# CPU_board_2A_7.net
KiCad netlist of a schematic drawn in EAGLE
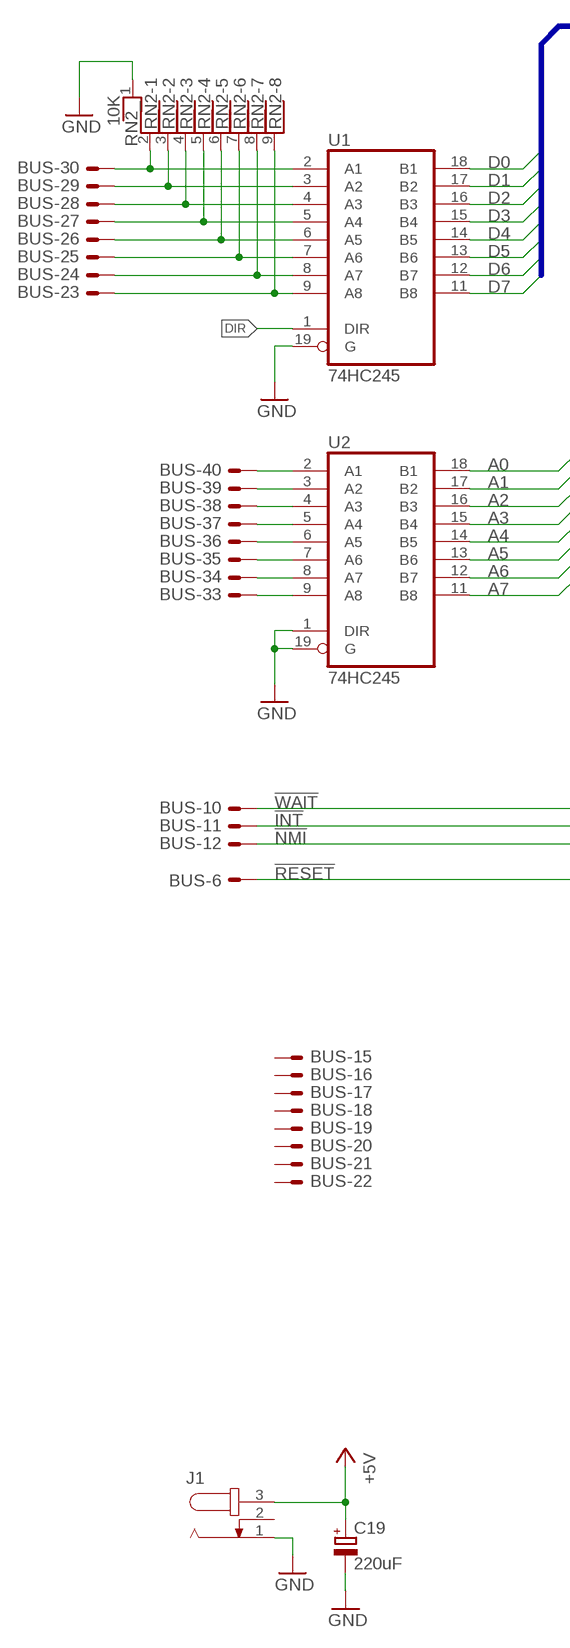
[diagram p0: schematic, sheet 1, part 1 of 2]
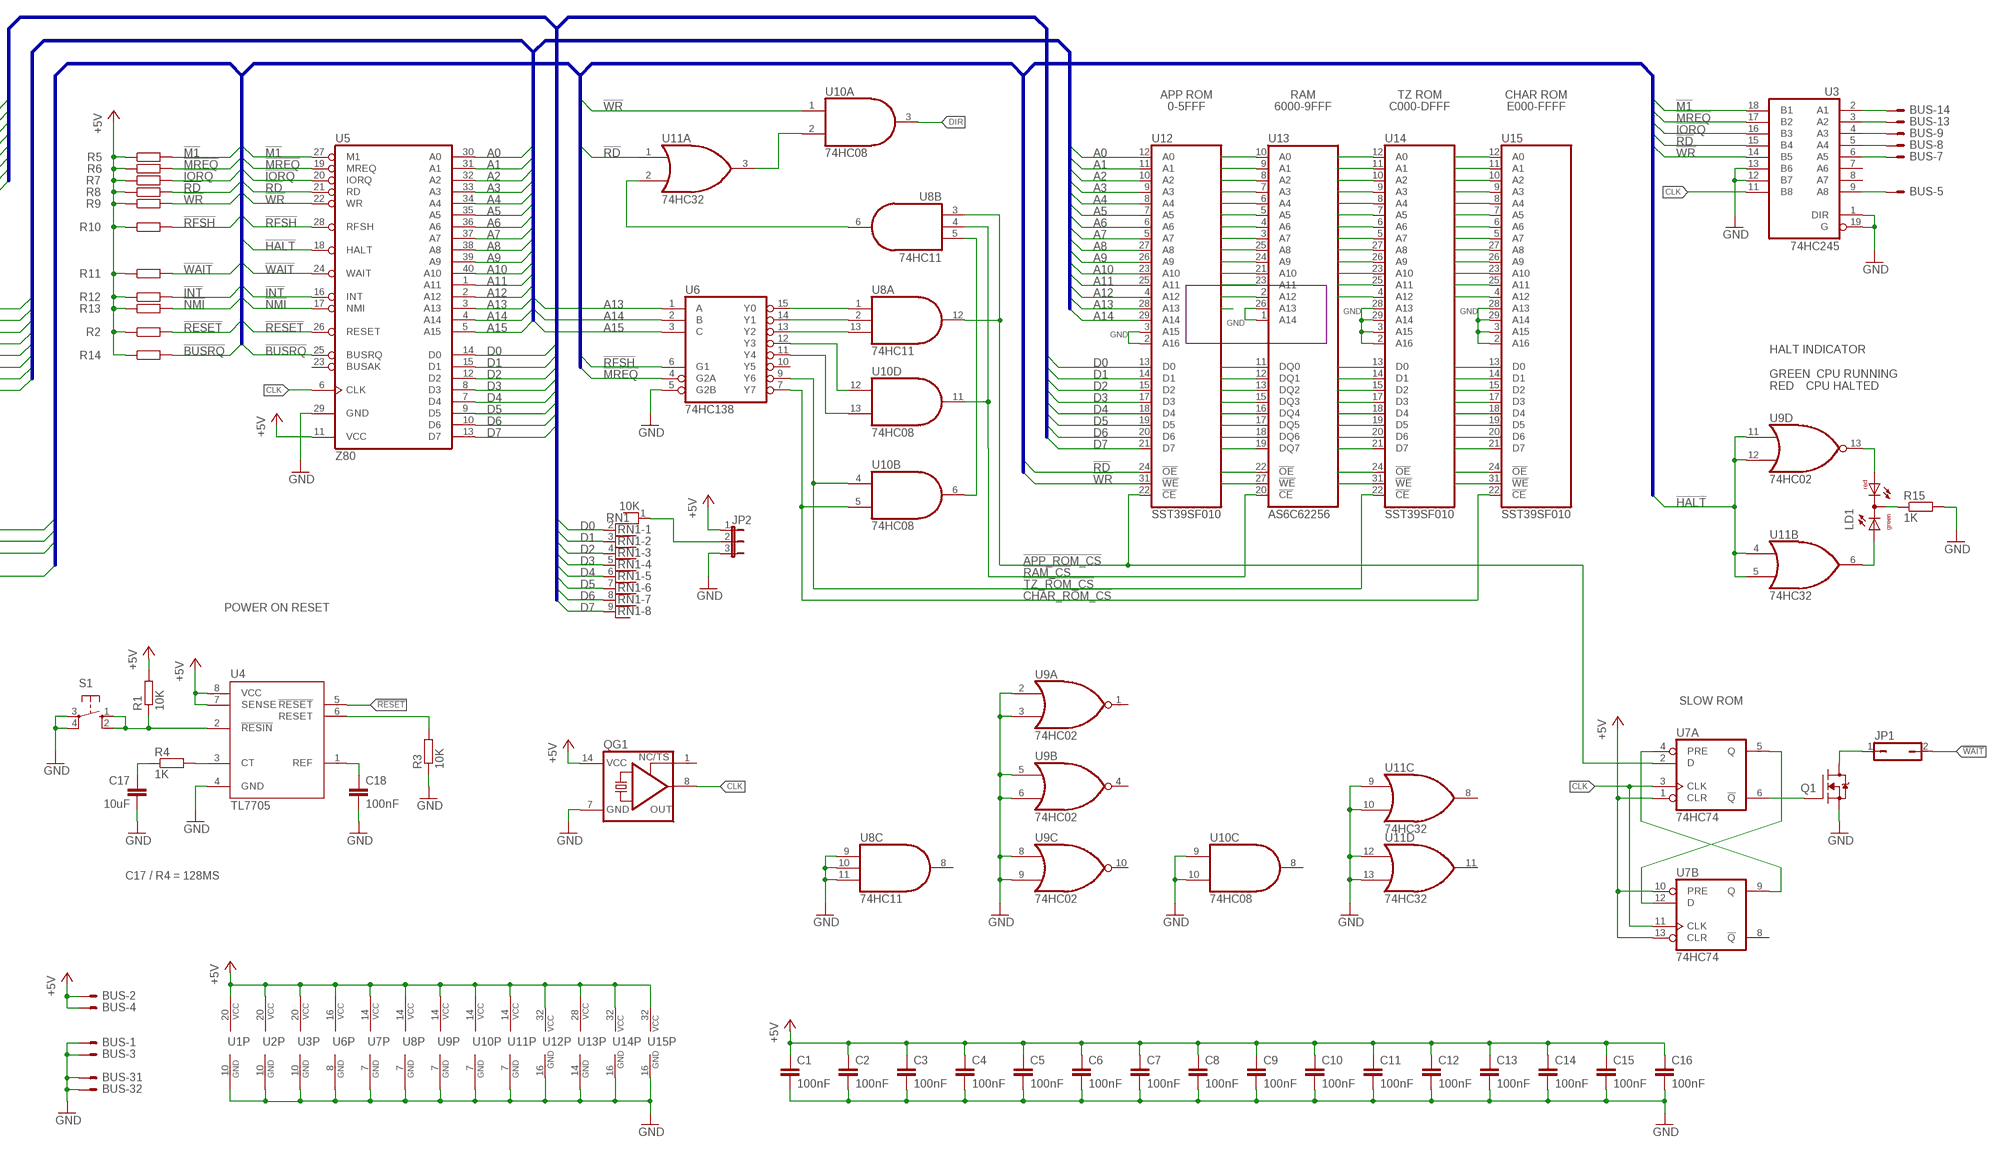
[diagram p1: schematic, sheet 1, part 2 of 2]

(export (version "E")
  (design (tool "Eeschema 10.0.6"))
  (components
    (comp (ref "BUS")
      (value "ML40E")
      (footprint "eagle-import:ML40")
      (libsource (lib "eagle-import") (part "ML40E"))
    )
    (comp (ref "C1")
      (value "100nF")
      (footprint "eagle-import:C050-025X075")
      (libsource (lib "eagle-import") (part "C-EU050-025X075"))
    )
    (comp (ref "C2")
      (value "100nF")
      (footprint "eagle-import:C050-025X075")
      (libsource (lib "eagle-import") (part "C-EU050-025X075"))
    )
    (comp (ref "C3")
      (value "100nF")
      (footprint "eagle-import:C050-025X075")
      (libsource (lib "eagle-import") (part "C-EU050-025X075"))
    )
    (comp (ref "C4")
      (value "100nF")
      (footprint "eagle-import:C050-025X075")
      (libsource (lib "eagle-import") (part "C-EU050-025X075"))
    )
    (comp (ref "C5")
      (value "100nF")
      (footprint "eagle-import:C050-025X075")
      (libsource (lib "eagle-import") (part "C-EU050-025X075"))
    )
    (comp (ref "C6")
      (value "100nF")
      (footprint "eagle-import:C050-025X075")
      (libsource (lib "eagle-import") (part "C-EU050-025X075"))
    )
    (comp (ref "C7")
      (value "100nF")
      (footprint "eagle-import:C050-025X075")
      (libsource (lib "eagle-import") (part "C-EU050-025X075"))
    )
    (comp (ref "C8")
      (value "100nF")
      (footprint "eagle-import:C050-025X075")
      (libsource (lib "eagle-import") (part "C-EU050-025X075"))
    )
    (comp (ref "C9")
      (value "100nF")
      (footprint "eagle-import:C050-025X075")
      (libsource (lib "eagle-import") (part "C-EU050-025X075"))
    )
    (comp (ref "C10")
      (value "100nF")
      (footprint "eagle-import:C050-025X075")
      (libsource (lib "eagle-import") (part "C-EU050-025X075"))
    )
    (comp (ref "C11")
      (value "100nF")
      (footprint "eagle-import:C050-025X075")
      (libsource (lib "eagle-import") (part "C-EU050-025X075"))
    )
    (comp (ref "C12")
      (value "100nF")
      (footprint "eagle-import:C050-025X075")
      (libsource (lib "eagle-import") (part "C-EU050-025X075"))
    )
    (comp (ref "C13")
      (value "100nF")
      (footprint "eagle-import:C050-025X075")
      (libsource (lib "eagle-import") (part "C-EU050-025X075"))
    )
    (comp (ref "C14")
      (value "100nF")
      (footprint "eagle-import:C050-025X075")
      (libsource (lib "eagle-import") (part "C-EU050-025X075"))
    )
    (comp (ref "C15")
      (value "100nF")
      (footprint "eagle-import:C050-025X075")
      (libsource (lib "eagle-import") (part "C-EU050-025X075"))
    )
    (comp (ref "C16")
      (value "100nF")
      (footprint "eagle-import:C050-025X075")
      (libsource (lib "eagle-import") (part "C-EU050-025X075"))
    )
    (comp (ref "C17")
      (value "10uF")
      (footprint "eagle-import:C050-025X075")
      (libsource (lib "eagle-import") (part "C-EU050-025X075"))
    )
    (comp (ref "C18")
      (value "100nF")
      (footprint "eagle-import:C050-025X075")
      (libsource (lib "eagle-import") (part "C-EU050-025X075"))
    )
    (comp (ref "C19")
      (value "220uF")
      (footprint "eagle-import:E3,5-8")
      (libsource (lib "eagle-import") (part "CPOL-EUE3.5-8"))
    )
    (comp (ref "J1")
      (value "JACK-PLUG0")
      (footprint "eagle-import:SPC4077")
      (libsource (lib "eagle-import") (part "JACK-PLUG0"))
    )
    (comp (ref "JP1")
      (value "JP1Q")
      (footprint "eagle-import:JP1")
      (libsource (lib "eagle-import") (part "JP1Q"))
    )
    (comp (ref "JP2")
      (value "JP2E")
      (footprint "eagle-import:JP2")
      (libsource (lib "eagle-import") (part "JP2E"))
    )
    (comp (ref "LD1")
      (value "DUOLED-RG-C")
      (footprint "eagle-import:DUOLED-C-5MM")
      (libsource (lib "eagle-import") (part "DUOLED-RG-C"))
    )
    (comp (ref "Q1")
      (value "2N7000")
      (footprint "eagle-import:TO-92-FORMED")
      (libsource (lib "eagle-import") (part "2N7000"))
    )
    (comp (ref "QG1")
      (value "XO-14")
      (footprint "eagle-import:DIL14S")
      (libsource (lib "eagle-import") (part "XO-14"))
    )
    (comp (ref "R1")
      (value "10K")
      (footprint "eagle-import:0207_10")
      (libsource (lib "eagle-import") (part "R-EU_0207/10"))
    )
    (comp (ref "R2")
      (value "10K")
      (footprint "eagle-import:0207_10")
      (libsource (lib "eagle-import") (part "R-EU_0207/10"))
    )
    (comp (ref "R3")
      (value "10K")
      (footprint "eagle-import:0207_10")
      (libsource (lib "eagle-import") (part "R-EU_0207/10"))
    )
    (comp (ref "R4")
      (value "1K")
      (footprint "eagle-import:0207_10")
      (libsource (lib "eagle-import") (part "R-EU_0207/10"))
    )
    (comp (ref "R5")
      (value "R-EU_0207/10")
      (footprint "eagle-import:0207_10")
      (libsource (lib "eagle-import") (part "R-EU_0207/10"))
    )
    (comp (ref "R6")
      (value "R-EU_0207/10")
      (footprint "eagle-import:0207_10")
      (libsource (lib "eagle-import") (part "R-EU_0207/10"))
    )
    (comp (ref "R7")
      (value "R-EU_0207/10")
      (footprint "eagle-import:0207_10")
      (libsource (lib "eagle-import") (part "R-EU_0207/10"))
    )
    (comp (ref "R8")
      (value "R-EU_0207/10")
      (footprint "eagle-import:0207_10")
      (libsource (lib "eagle-import") (part "R-EU_0207/10"))
    )
    (comp (ref "R9")
      (value "R-EU_0207/10")
      (footprint "eagle-import:0207_10")
      (libsource (lib "eagle-import") (part "R-EU_0207/10"))
    )
    (comp (ref "R10")
      (value "R-EU_0207/10")
      (footprint "eagle-import:0207_10")
      (libsource (lib "eagle-import") (part "R-EU_0207/10"))
    )
    (comp (ref "R11")
      (value "R-EU_0207/10")
      (footprint "eagle-import:0207_10")
      (libsource (lib "eagle-import") (part "R-EU_0207/10"))
    )
    (comp (ref "R12")
      (value "R-EU_0207/10")
      (footprint "eagle-import:0207_10")
      (libsource (lib "eagle-import") (part "R-EU_0207/10"))
    )
    (comp (ref "R13")
      (value "R-EU_0207/10")
      (footprint "eagle-import:0207_10")
      (libsource (lib "eagle-import") (part "R-EU_0207/10"))
    )
    (comp (ref "R14")
      (value "R-EU_0207/10")
      (footprint "eagle-import:0207_10")
      (libsource (lib "eagle-import") (part "R-EU_0207/10"))
    )
    (comp (ref "R15")
      (value "1K")
      (footprint "eagle-import:0207_10")
      (libsource (lib "eagle-import") (part "R-EU_0207/10"))
    )
    (comp (ref "RN1")
      (value "10K")
      (footprint "eagle-import:RN-9")
      (libsource (lib "eagle-import") (part "RNX8"))
    )
    (comp (ref "RN2")
      (value "10K")
      (footprint "eagle-import:RN-9")
      (libsource (lib "eagle-import") (part "RNX8"))
    )
    (comp (ref "S1")
      (value "10-XX")
      (footprint "eagle-import:B3F-10XX")
      (fields (field (name "MPN") "B3F-1000"))
      (libsource (lib "eagle-import") (part "10-XX"))
    )
    (comp (ref "U1")
      (value "74HC245")
      (footprint "eagle-import:DIL20")
      (libsource (lib "eagle-import") (part "74245NLS"))
    )
    (comp (ref "U2")
      (value "74HC245")
      (footprint "eagle-import:DIL20")
      (libsource (lib "eagle-import") (part "74245NLS"))
    )
    (comp (ref "U3")
      (value "74HC245")
      (footprint "eagle-import:DIL20")
      (libsource (lib "eagle-import") (part "74245NLS"))
    )
    (comp (ref "U4")
      (value "TL7705")
      (footprint "eagle-import:DIL08")
      (libsource (lib "eagle-import") (part "TL77XXA"))
    )
    (comp (ref "U5")
      (value "Z80")
      (footprint "eagle-import:DIL40")
      (libsource (lib "eagle-import") (part "Z80CPU"))
    )
    (comp (ref "U6")
      (value "74HC138")
      (footprint "eagle-import:DIL16")
      (libsource (lib "eagle-import") (part "74138NLS"))
    )
    (comp (ref "U7")
      (value "74HC74")
      (footprint "eagle-import:DIL14")
      (libsource (lib "eagle-import") (part "7474NLS"))
    )
    (comp (ref "U8")
      (value "74HC11")
      (footprint "eagle-import:DIL14")
      (libsource (lib "eagle-import") (part "7411NLS"))
    )
    (comp (ref "U9")
      (value "74HC02")
      (footprint "eagle-import:DIL14")
      (libsource (lib "eagle-import") (part "7402NLS"))
    )
    (comp (ref "U10")
      (value "74HC08")
      (footprint "eagle-import:DIL14")
      (libsource (lib "eagle-import") (part "7408NLS"))
    )
    (comp (ref "U11")
      (value "74HC32")
      (footprint "eagle-import:DIL14")
      (libsource (lib "eagle-import") (part "7432NLS"))
    )
    (comp (ref "U12")
      (value "SST39SF010")
      (footprint "eagle-import:DIL32")
      (libsource (lib "eagle-import") (part "SST39SF010P"))
    )
    (comp (ref "U13")
      (value "AS6C62256")
      (footprint "eagle-import:DIL28-6")
      (libsource (lib "eagle-import") (part "AS6C62256-55PCN"))
    )
    (comp (ref "U14")
      (value "SST39SF010")
      (footprint "eagle-import:PLCC-SR32")
      (libsource (lib "eagle-import") (part "SST39SF010NS"))
    )
    (comp (ref "U15")
      (value "SST39SF010")
      (footprint "eagle-import:PLCC-SR32")
      (libsource (lib "eagle-import") (part "SST39SF010NS"))
    )
  )
  (nets
    (net (code "18") (name "+5V") (class "Default")
      (node (ref "BUS") (pin "2") (pinfunction "S_2") (pintype "passive"))
      (node (ref "BUS") (pin "4") (pinfunction "S_4") (pintype "passive"))
      (node (ref "C1") (pin "1") (pinfunction "1_1") (pintype "passive"))
      (node (ref "C10") (pin "1") (pinfunction "1_1") (pintype "passive"))
      (node (ref "C11") (pin "1") (pinfunction "1_1") (pintype "passive"))
      (node (ref "C12") (pin "1") (pinfunction "1_1") (pintype "passive"))
      (node (ref "C13") (pin "1") (pinfunction "1_1") (pintype "passive"))
      (node (ref "C14") (pin "1") (pinfunction "1_1") (pintype "passive"))
      (node (ref "C15") (pin "1") (pinfunction "1_1") (pintype "passive"))
      (node (ref "C16") (pin "1") (pinfunction "1_1") (pintype "passive"))
      (node (ref "C19") (pin "+") (pinfunction "+_+") (pintype "passive"))
      (node (ref "C2") (pin "1") (pinfunction "1_1") (pintype "passive"))
      (node (ref "C3") (pin "1") (pinfunction "1_1") (pintype "passive"))
      (node (ref "C4") (pin "1") (pinfunction "1_1") (pintype "passive"))
      (node (ref "C5") (pin "1") (pinfunction "1_1") (pintype "passive"))
      (node (ref "C6") (pin "1") (pinfunction "1_1") (pintype "passive"))
      (node (ref "C7") (pin "1") (pinfunction "1_1") (pintype "passive"))
      (node (ref "C8") (pin "1") (pinfunction "1_1") (pintype "passive"))
      (node (ref "C9") (pin "1") (pinfunction "1_1") (pintype "passive"))
      (node (ref "J1") (pin "3") (pinfunction "3_3") (pintype "passive"))
      (node (ref "JP2") (pin "1") (pinfunction "1_1") (pintype "passive"))
      (node (ref "QG1") (pin "14") (pinfunction "VCC_14") (pintype "power_in"))
      (node (ref "R1") (pin "2") (pinfunction "2_2") (pintype "passive"))
      (node (ref "R10") (pin "1") (pinfunction "1_1") (pintype "passive"))
      (node (ref "R11") (pin "1") (pinfunction "1_1") (pintype "passive"))
      (node (ref "R12") (pin "1") (pinfunction "1_1") (pintype "passive"))
      (node (ref "R13") (pin "1") (pinfunction "1_1") (pintype "passive"))
      (node (ref "R14") (pin "1") (pinfunction "1_1") (pintype "passive"))
      (node (ref "R2") (pin "1") (pinfunction "1_1") (pintype "passive"))
      (node (ref "R5") (pin "1") (pinfunction "1_1") (pintype "passive"))
      (node (ref "R6") (pin "1") (pinfunction "1_1") (pintype "passive"))
      (node (ref "R7") (pin "1") (pinfunction "1_1") (pintype "passive"))
      (node (ref "R8") (pin "1") (pinfunction "1_1") (pintype "passive"))
      (node (ref "R9") (pin "1") (pinfunction "1_1") (pintype "passive"))
      (node (ref "U1") (pin "20") (pinfunction "VCC_20") (pintype "power_in"))
      (node (ref "U10") (pin "14") (pinfunction "VCC_14") (pintype "power_in"))
      (node (ref "U11") (pin "14") (pinfunction "VCC_14") (pintype "power_in"))
      (node (ref "U12") (pin "32") (pinfunction "VCC_32") (pintype "power_in"))
      (node (ref "U13") (pin "28") (pinfunction "VCC_28") (pintype "power_in"))
      (node (ref "U14") (pin "32") (pinfunction "VCC_32") (pintype "power_in"))
      (node (ref "U15") (pin "32") (pinfunction "VCC_32") (pintype "power_in"))
      (node (ref "U2") (pin "20") (pinfunction "VCC_20") (pintype "power_in"))
      (node (ref "U3") (pin "20") (pinfunction "VCC_20") (pintype "power_in"))
      (node (ref "U4") (pin "7") (pinfunction "SENSE_7") (pintype "input"))
      (node (ref "U4") (pin "8") (pinfunction "VCC_8") (pintype "power_in"))
      (node (ref "U5") (pin "11") (pinfunction "VCC_11") (pintype "power_in"))
      (node (ref "U6") (pin "16") (pinfunction "VCC_16") (pintype "power_in"))
      (node (ref "U7") (pin "1") (pinfunction "CLR_1") (pintype "input"))
      (node (ref "U7") (pin "10") (pinfunction "PRE_10") (pintype "input"))
      (node (ref "U7") (pin "13") (pinfunction "CLR_13") (pintype "input"))
      (node (ref "U7") (pin "14") (pinfunction "VCC_14") (pintype "power_in"))
      (node (ref "U8") (pin "14") (pinfunction "VCC_14") (pintype "power_in"))
      (node (ref "U9") (pin "14") (pinfunction "VCC_14") (pintype "power_in"))
    )
    (net (code "21") (name "A0") (class "Default")
      (node (ref "U12") (pin "12") (pinfunction "A0_12") (pintype "input"))
      (node (ref "U13") (pin "10") (pinfunction "A0_10") (pintype "input"))
      (node (ref "U14") (pin "12") (pinfunction "A0_12") (pintype "input"))
      (node (ref "U15") (pin "12") (pinfunction "A0_12") (pintype "input"))
      (node (ref "U2") (pin "18") (pinfunction "B1_18") (pintype "bidirectional"))
      (node (ref "U5") (pin "30") (pinfunction "A0_30") (pintype "output"))
    )
    (net (code "22") (name "A1") (class "Default")
      (node (ref "U12") (pin "11") (pinfunction "A1_11") (pintype "input"))
      (node (ref "U13") (pin "9") (pinfunction "A1_9") (pintype "input"))
      (node (ref "U14") (pin "11") (pinfunction "A1_11") (pintype "input"))
      (node (ref "U15") (pin "11") (pinfunction "A1_11") (pintype "input"))
      (node (ref "U2") (pin "17") (pinfunction "B2_17") (pintype "bidirectional"))
      (node (ref "U5") (pin "31") (pinfunction "A1_31") (pintype "output"))
    )
    (net (code "23") (name "A2") (class "Default")
      (node (ref "U12") (pin "10") (pinfunction "A2_10") (pintype "input"))
      (node (ref "U13") (pin "8") (pinfunction "A2_8") (pintype "input"))
      (node (ref "U14") (pin "10") (pinfunction "A2_10") (pintype "input"))
      (node (ref "U15") (pin "10") (pinfunction "A2_10") (pintype "input"))
      (node (ref "U2") (pin "16") (pinfunction "B3_16") (pintype "bidirectional"))
      (node (ref "U5") (pin "32") (pinfunction "A2_32") (pintype "output"))
    )
    (net (code "24") (name "A3") (class "Default")
      (node (ref "U12") (pin "9") (pinfunction "A3_9") (pintype "input"))
      (node (ref "U13") (pin "7") (pinfunction "A3_7") (pintype "input"))
      (node (ref "U14") (pin "9") (pinfunction "A3_9") (pintype "input"))
      (node (ref "U15") (pin "9") (pinfunction "A3_9") (pintype "input"))
      (node (ref "U2") (pin "15") (pinfunction "B4_15") (pintype "bidirectional"))
      (node (ref "U5") (pin "33") (pinfunction "A3_33") (pintype "output"))
    )
    (net (code "25") (name "A4") (class "Default")
      (node (ref "U12") (pin "8") (pinfunction "A4_8") (pintype "input"))
      (node (ref "U13") (pin "6") (pinfunction "A4_6") (pintype "input"))
      (node (ref "U14") (pin "8") (pinfunction "A4_8") (pintype "input"))
      (node (ref "U15") (pin "8") (pinfunction "A4_8") (pintype "input"))
      (node (ref "U2") (pin "14") (pinfunction "B5_14") (pintype "bidirectional"))
      (node (ref "U5") (pin "34") (pinfunction "A4_34") (pintype "output"))
    )
    (net (code "26") (name "A5") (class "Default")
      (node (ref "U12") (pin "7") (pinfunction "A5_7") (pintype "input"))
      (node (ref "U13") (pin "5") (pinfunction "A5_5") (pintype "input"))
      (node (ref "U14") (pin "7") (pinfunction "A5_7") (pintype "input"))
      (node (ref "U15") (pin "7") (pinfunction "A5_7") (pintype "input"))
      (node (ref "U2") (pin "13") (pinfunction "B6_13") (pintype "bidirectional"))
      (node (ref "U5") (pin "35") (pinfunction "A5_35") (pintype "output"))
    )
    (net (code "27") (name "A6") (class "Default")
      (node (ref "U12") (pin "6") (pinfunction "A6_6") (pintype "input"))
      (node (ref "U13") (pin "4") (pinfunction "A6_4") (pintype "input"))
      (node (ref "U14") (pin "6") (pinfunction "A6_6") (pintype "input"))
      (node (ref "U15") (pin "6") (pinfunction "A6_6") (pintype "input"))
      (node (ref "U2") (pin "12") (pinfunction "B7_12") (pintype "bidirectional"))
      (node (ref "U5") (pin "36") (pinfunction "A6_36") (pintype "output"))
    )
    (net (code "28") (name "A7") (class "Default")
      (node (ref "U12") (pin "5") (pinfunction "A7_5") (pintype "input"))
      (node (ref "U13") (pin "3") (pinfunction "A7_3") (pintype "input"))
      (node (ref "U14") (pin "5") (pinfunction "A7_5") (pintype "input"))
      (node (ref "U15") (pin "5") (pinfunction "A7_5") (pintype "input"))
      (node (ref "U2") (pin "11") (pinfunction "B8_11") (pintype "bidirectional"))
      (node (ref "U5") (pin "37") (pinfunction "A7_37") (pintype "output"))
    )
    (net (code "29") (name "A8") (class "Default")
      (node (ref "U12") (pin "27") (pinfunction "A8_27") (pintype "input"))
      (node (ref "U13") (pin "25") (pinfunction "A8_25") (pintype "input"))
      (node (ref "U14") (pin "27") (pinfunction "A8_27") (pintype "input"))
      (node (ref "U15") (pin "27") (pinfunction "A8_27") (pintype "input"))
      (node (ref "U5") (pin "38") (pinfunction "A8_38") (pintype "output"))
    )
    (net (code "30") (name "A9") (class "Default")
      (node (ref "U12") (pin "26") (pinfunction "A9_26") (pintype "input"))
      (node (ref "U13") (pin "24") (pinfunction "A9_24") (pintype "input"))
      (node (ref "U14") (pin "26") (pinfunction "A9_26") (pintype "input"))
      (node (ref "U15") (pin "26") (pinfunction "A9_26") (pintype "input"))
      (node (ref "U5") (pin "39") (pinfunction "A9_39") (pintype "output"))
    )
    (net (code "31") (name "A10") (class "Default")
      (node (ref "U12") (pin "23") (pinfunction "A10_23") (pintype "input"))
      (node (ref "U13") (pin "21") (pinfunction "A10_21") (pintype "input"))
      (node (ref "U14") (pin "23") (pinfunction "A10_23") (pintype "input"))
      (node (ref "U15") (pin "23") (pinfunction "A10_23") (pintype "input"))
      (node (ref "U5") (pin "40") (pinfunction "A10_40") (pintype "output"))
    )
    (net (code "32") (name "A11") (class "Default")
      (node (ref "U12") (pin "25") (pinfunction "A11_25") (pintype "input"))
      (node (ref "U13") (pin "23") (pinfunction "A11_23") (pintype "input"))
      (node (ref "U14") (pin "25") (pinfunction "A11_25") (pintype "input"))
      (node (ref "U15") (pin "25") (pinfunction "A11_25") (pintype "input"))
      (node (ref "U5") (pin "1") (pinfunction "A11_1") (pintype "output"))
    )
    (net (code "33") (name "A12") (class "Default")
      (node (ref "U12") (pin "4") (pinfunction "A12_4") (pintype "input"))
      (node (ref "U13") (pin "2") (pinfunction "A12_2") (pintype "input"))
      (node (ref "U14") (pin "4") (pinfunction "A12_4") (pintype "input"))
      (node (ref "U15") (pin "4") (pinfunction "A12_4") (pintype "input"))
      (node (ref "U5") (pin "2") (pinfunction "A12_2") (pintype "output"))
    )
    (net (code "34") (name "A13") (class "Default")
      (node (ref "U12") (pin "28") (pinfunction "A13_28") (pintype "input"))
      (node (ref "U5") (pin "3") (pinfunction "A13_3") (pintype "output"))
      (node (ref "U6") (pin "1") (pinfunction "A_1") (pintype "input"))
    )
    (net (code "35") (name "A14") (class "Default")
      (node (ref "U12") (pin "29") (pinfunction "A14_29") (pintype "input"))
      (node (ref "U5") (pin "4") (pinfunction "A14_4") (pintype "output"))
      (node (ref "U6") (pin "2") (pinfunction "B_2") (pintype "input"))
    )
    (net (code "36") (name "A15") (class "Default")
      (node (ref "U5") (pin "5") (pinfunction "A15_5") (pintype "output"))
      (node (ref "U6") (pin "3") (pinfunction "C_3") (pintype "input"))
    )
    (net (code "37") (name "CLK") (class "Default")
      (node (ref "QG1") (pin "8") (pinfunction "OUT_8") (pintype "output"))
      (node (ref "U3") (pin "11") (pinfunction "B8_11") (pintype "bidirectional"))
      (node (ref "U5") (pin "6") (pinfunction "CLK_6") (pintype "input"))
      (node (ref "U7") (pin "11") (pinfunction "CLK_11") (pintype "input"))
      (node (ref "U7") (pin "3") (pinfunction "CLK_3") (pintype "input"))
    )
    (net (code "38") (name "D0") (class "Default")
      (node (ref "RN1") (pin "2") (pinfunction "1_2") (pintype "passive"))
      (node (ref "U1") (pin "18") (pinfunction "B1_18") (pintype "bidirectional"))
      (node (ref "U12") (pin "13") (pinfunction "D0_13") (pintype "bidirectional"))
      (node (ref "U13") (pin "11") (pinfunction "DQ0_11") (pintype "bidirectional"))
      (node (ref "U14") (pin "13") (pinfunction "D0_13") (pintype "bidirectional"))
      (node (ref "U15") (pin "13") (pinfunction "D0_13") (pintype "bidirectional"))
      (node (ref "U5") (pin "14") (pinfunction "D0_14") (pintype "bidirectional"))
    )
    (net (code "39") (name "D1") (class "Default")
      (node (ref "RN1") (pin "3") (pinfunction "1_3") (pintype "passive"))
      (node (ref "U1") (pin "17") (pinfunction "B2_17") (pintype "bidirectional"))
      (node (ref "U12") (pin "14") (pinfunction "D1_14") (pintype "bidirectional"))
      (node (ref "U13") (pin "12") (pinfunction "DQ1_12") (pintype "bidirectional"))
      (node (ref "U14") (pin "14") (pinfunction "D1_14") (pintype "bidirectional"))
      (node (ref "U15") (pin "14") (pinfunction "D1_14") (pintype "bidirectional"))
      (node (ref "U5") (pin "15") (pinfunction "D1_15") (pintype "bidirectional"))
    )
    (net (code "40") (name "D2") (class "Default")
      (node (ref "RN1") (pin "4") (pinfunction "1_4") (pintype "passive"))
      (node (ref "U1") (pin "16") (pinfunction "B3_16") (pintype "bidirectional"))
      (node (ref "U12") (pin "15") (pinfunction "D2_15") (pintype "bidirectional"))
      (node (ref "U13") (pin "13") (pinfunction "DQ2_13") (pintype "bidirectional"))
      (node (ref "U14") (pin "15") (pinfunction "D2_15") (pintype "bidirectional"))
      (node (ref "U15") (pin "15") (pinfunction "D2_15") (pintype "bidirectional"))
      (node (ref "U5") (pin "12") (pinfunction "D2_12") (pintype "bidirectional"))
    )
    (net (code "41") (name "D3") (class "Default")
      (node (ref "RN1") (pin "5") (pinfunction "1_5") (pintype "passive"))
      (node (ref "U1") (pin "15") (pinfunction "B4_15") (pintype "bidirectional"))
      (node (ref "U12") (pin "17") (pinfunction "D3_17") (pintype "bidirectional"))
      (node (ref "U13") (pin "15") (pinfunction "DQ3_15") (pintype "bidirectional"))
      (node (ref "U14") (pin "17") (pinfunction "D3_17") (pintype "bidirectional"))
      (node (ref "U15") (pin "17") (pinfunction "D3_17") (pintype "bidirectional"))
      (node (ref "U5") (pin "8") (pinfunction "D3_8") (pintype "bidirectional"))
    )
    (net (code "42") (name "D4") (class "Default")
      (node (ref "RN1") (pin "6") (pinfunction "1_6") (pintype "passive"))
      (node (ref "U1") (pin "14") (pinfunction "B5_14") (pintype "bidirectional"))
      (node (ref "U12") (pin "18") (pinfunction "D4_18") (pintype "bidirectional"))
      (node (ref "U13") (pin "16") (pinfunction "DQ4_16") (pintype "bidirectional"))
      (node (ref "U14") (pin "18") (pinfunction "D4_18") (pintype "bidirectional"))
      (node (ref "U15") (pin "18") (pinfunction "D4_18") (pintype "bidirectional"))
      (node (ref "U5") (pin "7") (pinfunction "D4_7") (pintype "bidirectional"))
    )
    (net (code "43") (name "D5") (class "Default")
      (node (ref "RN1") (pin "7") (pinfunction "1_7") (pintype "passive"))
      (node (ref "U1") (pin "13") (pinfunction "B6_13") (pintype "bidirectional"))
      (node (ref "U12") (pin "19") (pinfunction "D5_19") (pintype "bidirectional"))
      (node (ref "U13") (pin "17") (pinfunction "DQ5_17") (pintype "bidirectional"))
      (node (ref "U14") (pin "19") (pinfunction "D5_19") (pintype "bidirectional"))
      (node (ref "U15") (pin "19") (pinfunction "D5_19") (pintype "bidirectional"))
      (node (ref "U5") (pin "9") (pinfunction "D5_9") (pintype "bidirectional"))
    )
    (net (code "44") (name "D6") (class "Default")
      (node (ref "RN1") (pin "8") (pinfunction "1_8") (pintype "passive"))
      (node (ref "U1") (pin "12") (pinfunction "B7_12") (pintype "bidirectional"))
      (node (ref "U12") (pin "20") (pinfunction "D6_20") (pintype "bidirectional"))
      (node (ref "U13") (pin "18") (pinfunction "DQ6_18") (pintype "bidirectional"))
      (node (ref "U14") (pin "20") (pinfunction "D6_20") (pintype "bidirectional"))
      (node (ref "U15") (pin "20") (pinfunction "D6_20") (pintype "bidirectional"))
      (node (ref "U5") (pin "10") (pinfunction "D6_10") (pintype "bidirectional"))
    )
    (net (code "45") (name "D7") (class "Default")
      (node (ref "RN1") (pin "9") (pinfunction "1_9") (pintype "passive"))
      (node (ref "U1") (pin "11") (pinfunction "B8_11") (pintype "bidirectional"))
      (node (ref "U12") (pin "21") (pinfunction "D7_21") (pintype "bidirectional"))
      (node (ref "U13") (pin "19") (pinfunction "DQ7_19") (pintype "bidirectional"))
      (node (ref "U14") (pin "21") (pinfunction "D7_21") (pintype "bidirectional"))
      (node (ref "U15") (pin "21") (pinfunction "D7_21") (pintype "bidirectional"))
      (node (ref "U5") (pin "13") (pinfunction "D7_13") (pintype "bidirectional"))
    )
    (net (code "46") (name "DIR") (class "Default")
      (node (ref "U1") (pin "1") (pinfunction "DIR_1") (pintype "input"))
      (node (ref "U10") (pin "3") (pinfunction "O_3") (pintype "output"))
    )
    (net (code "47") (name "GND") (class "Default")
      (node (ref "BUS") (pin "1") (pinfunction "S_1") (pintype "passive"))
      (node (ref "BUS") (pin "3") (pinfunction "S_3") (pintype "passive"))
      (node (ref "BUS") (pin "31") (pinfunction "S_31") (pintype "passive"))
      (node (ref "BUS") (pin "32") (pinfunction "S_32") (pintype "passive"))
      (node (ref "C1") (pin "2") (pinfunction "2_2") (pintype "passive"))
      (node (ref "C10") (pin "2") (pinfunction "2_2") (pintype "passive"))
      (node (ref "C11") (pin "2") (pinfunction "2_2") (pintype "passive"))
      (node (ref "C12") (pin "2") (pinfunction "2_2") (pintype "passive"))
      (node (ref "C13") (pin "2") (pinfunction "2_2") (pintype "passive"))
      (node (ref "C14") (pin "2") (pinfunction "2_2") (pintype "passive"))
      (node (ref "C15") (pin "2") (pinfunction "2_2") (pintype "passive"))
      (node (ref "C16") (pin "2") (pinfunction "2_2") (pintype "passive"))
      (node (ref "C17") (pin "2") (pinfunction "2_2") (pintype "passive"))
      (node (ref "C18") (pin "2") (pinfunction "2_2") (pintype "passive"))
      (node (ref "C19") (pin "-") (pinfunction "-_-") (pintype "passive"))
      (node (ref "C2") (pin "2") (pinfunction "2_2") (pintype "passive"))
      (node (ref "C3") (pin "2") (pinfunction "2_2") (pintype "passive"))
      (node (ref "C4") (pin "2") (pinfunction "2_2") (pintype "passive"))
      (node (ref "C5") (pin "2") (pinfunction "2_2") (pintype "passive"))
      (node (ref "C6") (pin "2") (pinfunction "2_2") (pintype "passive"))
      (node (ref "C7") (pin "2") (pinfunction "2_2") (pintype "passive"))
      (node (ref "C8") (pin "2") (pinfunction "2_2") (pintype "passive"))
      (node (ref "C9") (pin "2") (pinfunction "2_2") (pintype "passive"))
      (node (ref "J1") (pin "1") (pinfunction "1_1") (pintype "passive"))
      (node (ref "JP2") (pin "3") (pinfunction "3_3") (pintype "passive"))
      (node (ref "Q1") (pin "1") (pinfunction "S_1") (pintype "passive"))
      (node (ref "QG1") (pin "7") (pinfunction "GND_7") (pintype "power_in"))
      (node (ref "R15") (pin "2") (pinfunction "2_2") (pintype "passive"))
      (node (ref "R3") (pin "1") (pinfunction "1_1") (pintype "passive"))
      (node (ref "RN2") (pin "1") (pinfunction "1_1") (pintype "passive"))
      (node (ref "S1") (pin "3") (pinfunction "P_3") (pintype "passive"))
      (node (ref "S1") (pin "4") (pinfunction "P1_4") (pintype "passive"))
      (node (ref "U1") (pin "10") (pinfunction "GND_10") (pintype "power_in"))
      (node (ref "U1") (pin "19") (pinfunction "G_19") (pintype "input"))
      (node (ref "U10") (pin "10") (pinfunction "I1_10") (pintype "input"))
      (node (ref "U10") (pin "7") (pinfunction "GND_7") (pintype "power_in"))
      (node (ref "U10") (pin "9") (pinfunction "I0_9") (pintype "input"))
      (node (ref "U11") (pin "10") (pinfunction "I1_10") (pintype "input"))
      (node (ref "U11") (pin "12") (pinfunction "I0_12") (pintype "input"))
      (node (ref "U11") (pin "13") (pinfunction "I1_13") (pintype "input"))
      (node (ref "U11") (pin "7") (pinfunction "GND_7") (pintype "power_in"))
      (node (ref "U11") (pin "9") (pinfunction "I0_9") (pintype "input"))
      (node (ref "U12") (pin "16") (pinfunction "GND_16") (pintype "power_in"))
      (node (ref "U12") (pin "2") (pinfunction "A16_2") (pintype "input"))
      (node (ref "U12") (pin "3") (pinfunction "A15_3") (pintype "input"))
      (node (ref "U13") (pin "1") (pinfunction "A14_1") (pintype "input"))
      (node (ref "U13") (pin "14") (pinfunction "GND_14") (pintype "power_in"))
      (node (ref "U13") (pin "26") (pinfunction "A13_26") (pintype "input"))
      (node (ref "U14") (pin "16") (pinfunction "GND_16") (pintype "power_in"))
      (node (ref "U14") (pin "2") (pinfunction "A16_2") (pintype "input"))
      (node (ref "U14") (pin "28") (pinfunction "A13_28") (pintype "input"))
      (node (ref "U14") (pin "29") (pinfunction "A14_29") (pintype "input"))
      (node (ref "U14") (pin "3") (pinfunction "A15_3") (pintype "input"))
      (node (ref "U15") (pin "16") (pinfunction "GND_16") (pintype "power_in"))
      (node (ref "U15") (pin "2") (pinfunction "A16_2") (pintype "input"))
      (node (ref "U15") (pin "28") (pinfunction "A13_28") (pintype "input"))
      (node (ref "U15") (pin "29") (pinfunction "A14_29") (pintype "input"))
      (node (ref "U15") (pin "3") (pinfunction "A15_3") (pintype "input"))
      (node (ref "U2") (pin "1") (pinfunction "DIR_1") (pintype "input"))
      (node (ref "U2") (pin "10") (pinfunction "GND_10") (pintype "power_in"))
      (node (ref "U2") (pin "19") (pinfunction "G_19") (pintype "input"))
      (node (ref "U3") (pin "1") (pinfunction "DIR_1") (pintype "input"))
      (node (ref "U3") (pin "10") (pinfunction "GND_10") (pintype "power_in"))
      (node (ref "U3") (pin "12") (pinfunction "B7_12") (pintype "bidirectional"))
      (node (ref "U3") (pin "13") (pinfunction "B6_13") (pintype "bidirectional"))
      (node (ref "U3") (pin "19") (pinfunction "G_19") (pintype "input"))
      (node (ref "U4") (pin "4") (pinfunction "GND_4") (pintype "power_in"))
      (node (ref "U5") (pin "29") (pinfunction "GND_29") (pintype "power_in"))
      (node (ref "U6") (pin "5") (pinfunction "G2B_5") (pintype "input"))
      (node (ref "U6") (pin "8") (pinfunction "GND_8") (pintype "power_in"))
      (node (ref "U7") (pin "7") (pinfunction "GND_7") (pintype "power_in"))
      (node (ref "U8") (pin "10") (pinfunction "I1_10") (pintype "input"))
      (node (ref "U8") (pin "11") (pinfunction "I2_11") (pintype "input"))
      (node (ref "U8") (pin "7") (pinfunction "GND_7") (pintype "power_in"))
      (node (ref "U8") (pin "9") (pinfunction "I0_9") (pintype "input"))
      (node (ref "U9") (pin "2") (pinfunction "I0_2") (pintype "input"))
      (node (ref "U9") (pin "3") (pinfunction "I1_3") (pintype "input"))
      (node (ref "U9") (pin "5") (pinfunction "I0_5") (pintype "input"))
      (node (ref "U9") (pin "6") (pinfunction "I1_6") (pintype "input"))
      (node (ref "U9") (pin "7") (pinfunction "GND_7") (pintype "power_in"))
      (node (ref "U9") (pin "8") (pinfunction "I0_8") (pintype "input"))
      (node (ref "U9") (pin "9") (pinfunction "I1_9") (pintype "input"))
    )
    (net (code "48") (name "Net-(BUSAA-S)") (class "Default")
      (node (ref "BUS") (pin "33") (pinfunction "S_33") (pintype "passive"))
      (node (ref "U2") (pin "9") (pinfunction "A8_9") (pintype "bidirectional"))
    )
    (net (code "49") (name "Net-(BUSAB-S)") (class "Default")
      (node (ref "BUS") (pin "34") (pinfunction "S_34") (pintype "passive"))
      (node (ref "U2") (pin "8") (pinfunction "A7_8") (pintype "bidirectional"))
    )
    (net (code "50") (name "Net-(BUSAC-S)") (class "Default")
      (node (ref "BUS") (pin "35") (pinfunction "S_35") (pintype "passive"))
      (node (ref "U2") (pin "7") (pinfunction "A6_7") (pintype "bidirectional"))
    )
    (net (code "51") (name "Net-(BUSAD-S)") (class "Default")
      (node (ref "BUS") (pin "36") (pinfunction "S_36") (pintype "passive"))
      (node (ref "U2") (pin "6") (pinfunction "A5_6") (pintype "bidirectional"))
    )
    (net (code "52") (name "Net-(BUSAE-S)") (class "Default")
      (node (ref "BUS") (pin "37") (pinfunction "S_37") (pintype "passive"))
      (node (ref "U2") (pin "5") (pinfunction "A4_5") (pintype "bidirectional"))
    )
    (net (code "53") (name "Net-(BUSAF-S)") (class "Default")
      (node (ref "BUS") (pin "38") (pinfunction "S_38") (pintype "passive"))
      (node (ref "U2") (pin "4") (pinfunction "A3_4") (pintype "bidirectional"))
    )
    (net (code "54") (name "Net-(BUSAG-S)") (class "Default")
      (node (ref "BUS") (pin "39") (pinfunction "S_39") (pintype "passive"))
      (node (ref "U2") (pin "3") (pinfunction "A2_3") (pintype "bidirectional"))
    )
    (net (code "55") (name "Net-(BUSAI-S)") (class "Default")
      (node (ref "BUS") (pin "40") (pinfunction "S_40") (pintype "passive"))
      (node (ref "U2") (pin "2") (pinfunction "A1_2") (pintype "bidirectional"))
    )
    (net (code "56") (name "Net-(BUSAJ-S)") (class "Default")
      (node (ref "BUS") (pin "5") (pinfunction "S_5") (pintype "passive"))
      (node (ref "U3") (pin "9") (pinfunction "A8_9") (pintype "bidirectional"))
    )
    (net (code "57") (name "Net-(BUSAL-S)") (class "Default")
      (node (ref "BUS") (pin "7") (pinfunction "S_7") (pintype "passive"))
      (node (ref "U3") (pin "6") (pinfunction "A5_6") (pintype "bidirectional"))
    )
    (net (code "58") (name "Net-(BUSAM-S)") (class "Default")
      (node (ref "BUS") (pin "8") (pinfunction "S_8") (pintype "passive"))
      (node (ref "U3") (pin "5") (pinfunction "A4_5") (pintype "bidirectional"))
    )
    (net (code "59") (name "Net-(BUSAN-S)") (class "Default")
      (node (ref "BUS") (pin "9") (pinfunction "S_9") (pintype "passive"))
      (node (ref "U3") (pin "4") (pinfunction "A3_4") (pintype "bidirectional"))
    )
    (net (code "60") (name "Net-(BUSE-S)") (class "Default")
      (node (ref "BUS") (pin "13") (pinfunction "S_13") (pintype "passive"))
      (node (ref "U3") (pin "3") (pinfunction "A2_3") (pintype "bidirectional"))
    )
    (net (code "61") (name "Net-(BUSF-S)") (class "Default")
      (node (ref "BUS") (pin "14") (pinfunction "S_14") (pintype "passive"))
      (node (ref "U3") (pin "2") (pinfunction "A1_2") (pintype "bidirectional"))
    )
    (net (code "62") (name "Net-(BUSP-S)") (class "Default")
      (node (ref "BUS") (pin "23") (pinfunction "S_23") (pintype "passive"))
      (node (ref "RN2") (pin "9") (pinfunction "1_9") (pintype "passive"))
      (node (ref "U1") (pin "9") (pinfunction "A8_9") (pintype "bidirectional"))
    )
    (net (code "63") (name "Net-(BUSQ-S)") (class "Default")
      (node (ref "BUS") (pin "24") (pinfunction "S_24") (pintype "passive"))
      (node (ref "RN2") (pin "8") (pinfunction "1_8") (pintype "passive"))
      (node (ref "U1") (pin "8") (pinfunction "A7_8") (pintype "bidirectional"))
    )
    (net (code "64") (name "Net-(BUSR-S)") (class "Default")
      (node (ref "BUS") (pin "25") (pinfunction "S_25") (pintype "passive"))
      (node (ref "RN2") (pin "7") (pinfunction "1_7") (pintype "passive"))
      (node (ref "U1") (pin "7") (pinfunction "A6_7") (pintype "bidirectional"))
    )
    (net (code "65") (name "Net-(BUSS-S)") (class "Default")
      (node (ref "BUS") (pin "26") (pinfunction "S_26") (pintype "passive"))
      (node (ref "RN2") (pin "6") (pinfunction "1_6") (pintype "passive"))
      (node (ref "U1") (pin "6") (pinfunction "A5_6") (pintype "bidirectional"))
    )
    (net (code "66") (name "Net-(BUST-S)") (class "Default")
      (node (ref "BUS") (pin "27") (pinfunction "S_27") (pintype "passive"))
      (node (ref "RN2") (pin "5") (pinfunction "1_5") (pintype "passive"))
      (node (ref "U1") (pin "5") (pinfunction "A4_5") (pintype "bidirectional"))
    )
    (net (code "67") (name "Net-(BUSU-S)") (class "Default")
      (node (ref "BUS") (pin "28") (pinfunction "S_28") (pintype "passive"))
      (node (ref "RN2") (pin "4") (pinfunction "1_4") (pintype "passive"))
      (node (ref "U1") (pin "4") (pinfunction "A3_4") (pintype "bidirectional"))
    )
    (net (code "68") (name "Net-(BUSV-S)") (class "Default")
      (node (ref "BUS") (pin "29") (pinfunction "S_29") (pintype "passive"))
      (node (ref "RN2") (pin "3") (pinfunction "1_3") (pintype "passive"))
      (node (ref "U1") (pin "3") (pinfunction "A2_3") (pintype "bidirectional"))
    )
    (net (code "69") (name "Net-(BUSX-S)") (class "Default")
      (node (ref "BUS") (pin "30") (pinfunction "S_30") (pintype "passive"))
      (node (ref "RN2") (pin "2") (pinfunction "1_2") (pintype "passive"))
      (node (ref "U1") (pin "2") (pinfunction "A1_2") (pintype "bidirectional"))
    )
    (net (code "70") (name "Net-(C17-Pad1)") (class "Default")
      (node (ref "C17") (pin "1") (pinfunction "1_1") (pintype "passive"))
      (node (ref "R4") (pin "1") (pinfunction "1_1") (pintype "passive"))
    )
    (net (code "71") (name "Net-(JP2-Pad2)") (class "Default")
      (node (ref "JP2") (pin "2") (pinfunction "2_2") (pintype "passive"))
      (node (ref "RN1") (pin "1") (pinfunction "1_1") (pintype "passive"))
    )
    (net (code "72") (name "Net-(LD1-AG)") (class "Default")
      (node (ref "LD1") (pin "AX") (pinfunction "AG_AX") (pintype "passive"))
      (node (ref "U11") (pin "6") (pinfunction "O_6") (pintype "output"))
    )
    (net (code "73") (name "Net-(LD1-PadC)") (class "Default")
      (node (ref "LD1") (pin "C") (pinfunction "C_C") (pintype "passive"))
      (node (ref "R15") (pin "1") (pinfunction "1_1") (pintype "passive"))
    )
    (net (code "74") (name "Net-(Q1-D)") (class "Default")
      (node (ref "JP1") (pin "1") (pinfunction "1_1") (pintype "passive"))
      (node (ref "Q1") (pin "3") (pinfunction "D_3") (pintype "passive"))
    )
    (net (code "75") (name "Net-(Q1-G)") (class "Default")
      (node (ref "Q1") (pin "2") (pinfunction "G_2") (pintype "passive"))
      (node (ref "U7") (pin "6") (pinfunction "~{Q}_6") (pintype "output"))
    )
    (net (code "76") (name "Net-(S1-S)") (class "Default")
      (node (ref "R1") (pin "1") (pinfunction "1_1") (pintype "passive"))
      (node (ref "S1") (pin "1") (pinfunction "S_1") (pintype "passive"))
      (node (ref "S1") (pin "2") (pinfunction "S1_2") (pintype "passive"))
      (node (ref "U4") (pin "2") (pinfunction "~{RESIN}_2") (pintype "input"))
    )
    (net (code "77") (name "Net-(U4-CT)") (class "Default")
      (node (ref "R4") (pin "2") (pinfunction "2_2") (pintype "passive"))
      (node (ref "U4") (pin "3") (pinfunction "CT_3") (pintype "input"))
    )
    (net (code "78") (name "Net-(U4-REF)") (class "Default")
      (node (ref "C18") (pin "1") (pinfunction "1_1") (pintype "passive"))
      (node (ref "U4") (pin "1") (pinfunction "REF_1") (pintype "bidirectional"))
    )
    (net (code "79") (name "Net-(U4-RESET)") (class "Default")
      (node (ref "R3") (pin "2") (pinfunction "2_2") (pintype "passive"))
      (node (ref "U4") (pin "6") (pinfunction "RESET_6") (pintype "open_collector"))
    )
    (net (code "80") (name "Net-(U6A-Y0)") (class "Default")
      (node (ref "U6") (pin "15") (pinfunction "Y0_15") (pintype "output"))
      (node (ref "U8") (pin "1") (pinfunction "I0_1") (pintype "input"))
    )
    (net (code "81") (name "Net-(U6A-Y1)") (class "Default")
      (node (ref "U6") (pin "14") (pinfunction "Y1_14") (pintype "output"))
      (node (ref "U8") (pin "2") (pinfunction "I1_2") (pintype "input"))
    )
    (net (code "82") (name "Net-(U6A-Y2)") (class "Default")
      (node (ref "U6") (pin "13") (pinfunction "Y2_13") (pintype "output"))
      (node (ref "U8") (pin "13") (pinfunction "I2_13") (pintype "input"))
    )
    (net (code "83") (name "Net-(U7A-PRE)") (class "Default")
      (node (ref "U7") (pin "4") (pinfunction "PRE_4") (pintype "input"))
      (node (ref "U7") (pin "9") (pinfunction "Q_9") (pintype "output"))
    )
    (net (code "84") (name "Net-(U7A-Q)") (class "Default")
      (node (ref "U7") (pin "12") (pinfunction "D_12") (pintype "input"))
      (node (ref "U7") (pin "5") (pinfunction "Q_5") (pintype "output"))
    )
    (net (code "85") (name "Net-(U9D-O)") (class "Default")
      (node (ref "LD1") (pin "AR") (pinfunction "AR_AR") (pintype "passive"))
      (node (ref "U9") (pin "13") (pinfunction "O_13") (pintype "output"))
    )
    (net (code "86") (name "Net-(U10A-I1)") (class "Default")
      (node (ref "U10") (pin "2") (pinfunction "I1_2") (pintype "input"))
      (node (ref "U11") (pin "3") (pinfunction "O_3") (pintype "output"))
    )
    (net (code "87") (name "Net-(U10B-O)") (class "Default")
      (node (ref "U10") (pin "6") (pinfunction "O_6") (pintype "output"))
      (node (ref "U8") (pin "5") (pinfunction "I2_5") (pintype "input"))
    )
    (net (code "88") (name "Net-(U10D-I0)") (class "Default")
      (node (ref "U10") (pin "12") (pinfunction "I0_12") (pintype "input"))
      (node (ref "U6") (pin "12") (pinfunction "Y3_12") (pintype "output"))
    )
    (net (code "89") (name "Net-(U10D-I1)") (class "Default")
      (node (ref "U10") (pin "13") (pinfunction "I1_13") (pintype "input"))
      (node (ref "U6") (pin "11") (pinfunction "Y4_11") (pintype "output"))
    )
    (net (code "90") (name "Net-(U11A-I1)") (class "Default")
      (node (ref "U11") (pin "2") (pinfunction "I1_2") (pintype "input"))
      (node (ref "U8") (pin "6") (pinfunction "O_6") (pintype "output"))
    )
    (net (code "91") (name "unconnected-(BUSG-S-Pad15)") (class "Default")
      (node (ref "BUS") (pin "15") (pinfunction "S_15") (pintype "passive"))
    )
    (net (code "92") (name "unconnected-(BUSH-S-Pad16)") (class "Default")
      (node (ref "BUS") (pin "16") (pinfunction "S_16") (pintype "passive"))
    )
    (net (code "93") (name "unconnected-(BUSI-S-Pad17)") (class "Default")
      (node (ref "BUS") (pin "17") (pinfunction "S_17") (pintype "passive"))
    )
    (net (code "94") (name "unconnected-(BUSJ-S-Pad18)") (class "Default")
      (node (ref "BUS") (pin "18") (pinfunction "S_18") (pintype "passive"))
    )
    (net (code "95") (name "unconnected-(BUSK-S-Pad19)") (class "Default")
      (node (ref "BUS") (pin "19") (pinfunction "S_19") (pintype "passive"))
    )
    (net (code "96") (name "unconnected-(BUSM-S-Pad20)") (class "Default")
      (node (ref "BUS") (pin "20") (pinfunction "S_20") (pintype "passive"))
    )
    (net (code "97") (name "unconnected-(BUSN-S-Pad21)") (class "Default")
      (node (ref "BUS") (pin "21") (pinfunction "S_21") (pintype "passive"))
    )
    (net (code "98") (name "unconnected-(BUSO-S-Pad22)") (class "Default")
      (node (ref "BUS") (pin "22") (pinfunction "S_22") (pintype "passive"))
    )
    (net (code "99") (name "unconnected-(J1-Pad2)") (class "Default")
      (node (ref "J1") (pin "2") (pinfunction "2_2") (pintype "passive"))
    )
    (net (code "100") (name "unconnected-(QG1-TS-Pad1)") (class "Default")
      (node (ref "QG1") (pin "1") (pinfunction "TS_1") (pintype "passive"))
    )
    (net (code "101") (name "unconnected-(U3A-A6-Pad7)") (class "Default")
      (node (ref "U3") (pin "7") (pinfunction "A6_7") (pintype "bidirectional"))
    )
    (net (code "102") (name "unconnected-(U3A-A7-Pad8)") (class "Default")
      (node (ref "U3") (pin "8") (pinfunction "A7_8") (pintype "bidirectional"))
    )
    (net (code "103") (name "unconnected-(U5-BUSAK-Pad23)") (class "Default")
      (node (ref "U5") (pin "23") (pinfunction "BUSAK_23") (pintype "output"))
    )
    (net (code "104") (name "unconnected-(U6A-Y5-Pad10)") (class "Default")
      (node (ref "U6") (pin "10") (pinfunction "Y5_10") (pintype "output"))
    )
    (net (code "105") (name "unconnected-(U7B-~{Q}-Pad8)") (class "Default")
      (node (ref "U7") (pin "8") (pinfunction "~{Q}_8") (pintype "output"))
    )
    (net (code "106") (name "unconnected-(U8C-O-Pad8)") (class "Default")
      (node (ref "U8") (pin "8") (pinfunction "O_8") (pintype "output"))
    )
    (net (code "107") (name "unconnected-(U9A-O-Pad1)") (class "Default")
      (node (ref "U9") (pin "1") (pinfunction "O_1") (pintype "output"))
    )
    (net (code "108") (name "unconnected-(U9B-O-Pad4)") (class "Default")
      (node (ref "U9") (pin "4") (pinfunction "O_4") (pintype "output"))
    )
    (net (code "109") (name "unconnected-(U9C-O-Pad10)") (class "Default")
      (node (ref "U9") (pin "10") (pinfunction "O_10") (pintype "output"))
    )
    (net (code "110") (name "unconnected-(U10C-O-Pad8)") (class "Default")
      (node (ref "U10") (pin "8") (pinfunction "O_8") (pintype "output"))
    )
    (net (code "111") (name "unconnected-(U11C-O-Pad8)") (class "Default")
      (node (ref "U11") (pin "8") (pinfunction "O_8") (pintype "output"))
    )
    (net (code "112") (name "unconnected-(U11D-O-Pad11)") (class "Default")
      (node (ref "U11") (pin "11") (pinfunction "O_11") (pintype "output"))
    )
    (net (code "113") (name "~{APP_ROM_CS}") (class "Default")
      (node (ref "U12") (pin "22") (pinfunction "~{CE}_22") (pintype "input"))
      (node (ref "U7") (pin "2") (pinfunction "D_2") (pintype "input"))
      (node (ref "U8") (pin "12") (pinfunction "O_12") (pintype "output"))
      (node (ref "U8") (pin "3") (pinfunction "I0_3") (pintype "input"))
    )
    (net (code "114") (name "~{BUSRQ}") (class "Default")
      (node (ref "R14") (pin "2") (pinfunction "2_2") (pintype "passive"))
      (node (ref "U5") (pin "25") (pinfunction "BUSRQ_25") (pintype "input"))
    )
    (net (code "115") (name "~{CHAR_ROM_CS}") (class "Default")
      (node (ref "U10") (pin "5") (pinfunction "I1_5") (pintype "input"))
      (node (ref "U15") (pin "22") (pinfunction "~{CE}_22") (pintype "input"))
      (node (ref "U6") (pin "7") (pinfunction "Y7_7") (pintype "output"))
    )
    (net (code "116") (name "~{HALT}") (class "Default")
      (node (ref "U11") (pin "4") (pinfunction "I0_4") (pintype "input"))
      (node (ref "U11") (pin "5") (pinfunction "I1_5") (pintype "input"))
      (node (ref "U5") (pin "18") (pinfunction "HALT_18") (pintype "output"))
      (node (ref "U9") (pin "11") (pinfunction "I0_11") (pintype "input"))
      (node (ref "U9") (pin "12") (pinfunction "I1_12") (pintype "input"))
    )
    (net (code "117") (name "~{INT}") (class "Default")
      (node (ref "BUS") (pin "11") (pinfunction "S_11") (pintype "passive"))
      (node (ref "R12") (pin "2") (pinfunction "2_2") (pintype "passive"))
      (node (ref "U5") (pin "16") (pinfunction "INT_16") (pintype "input"))
    )
    (net (code "118") (name "~{IORQ}") (class "Default")
      (node (ref "R7") (pin "2") (pinfunction "2_2") (pintype "passive"))
      (node (ref "U3") (pin "16") (pinfunction "B3_16") (pintype "bidirectional"))
      (node (ref "U5") (pin "20") (pinfunction "IORQ_20") (pintype "output"))
    )
    (net (code "119") (name "~{M1}") (class "Default")
      (node (ref "R5") (pin "2") (pinfunction "2_2") (pintype "passive"))
      (node (ref "U3") (pin "18") (pinfunction "B1_18") (pintype "bidirectional"))
      (node (ref "U5") (pin "27") (pinfunction "M1_27") (pintype "output"))
    )
    (net (code "120") (name "~{MREQ}") (class "Default")
      (node (ref "R6") (pin "2") (pinfunction "2_2") (pintype "passive"))
      (node (ref "U3") (pin "17") (pinfunction "B2_17") (pintype "bidirectional"))
      (node (ref "U5") (pin "19") (pinfunction "MREQ_19") (pintype "output"))
      (node (ref "U6") (pin "4") (pinfunction "G2A_4") (pintype "input"))
    )
    (net (code "121") (name "~{NMI}") (class "Default")
      (node (ref "BUS") (pin "12") (pinfunction "S_12") (pintype "passive"))
      (node (ref "R13") (pin "2") (pinfunction "2_2") (pintype "passive"))
      (node (ref "U5") (pin "17") (pinfunction "NMI_17") (pintype "input"))
    )
    (net (code "122") (name "~{RAM_CS}") (class "Default")
      (node (ref "U10") (pin "11") (pinfunction "O_11") (pintype "output"))
      (node (ref "U13") (pin "20") (pinfunction "~{CE}_20") (pintype "input"))
      (node (ref "U8") (pin "4") (pinfunction "I1_4") (pintype "input"))
    )
    (net (code "123") (name "~{RD}") (class "Default")
      (node (ref "R8") (pin "2") (pinfunction "2_2") (pintype "passive"))
      (node (ref "U11") (pin "1") (pinfunction "I0_1") (pintype "input"))
      (node (ref "U12") (pin "24") (pinfunction "~{OE}_24") (pintype "input"))
      (node (ref "U13") (pin "22") (pinfunction "~{OE}_22") (pintype "input"))
      (node (ref "U14") (pin "24") (pinfunction "~{OE}_24") (pintype "input"))
      (node (ref "U15") (pin "24") (pinfunction "~{OE}_24") (pintype "input"))
      (node (ref "U3") (pin "15") (pinfunction "B4_15") (pintype "bidirectional"))
      (node (ref "U5") (pin "21") (pinfunction "RD_21") (pintype "output"))
    )
    (net (code "124") (name "~{RESET}") (class "Default")
      (node (ref "BUS") (pin "6") (pinfunction "S_6") (pintype "passive"))
      (node (ref "R2") (pin "2") (pinfunction "2_2") (pintype "passive"))
      (node (ref "U4") (pin "5") (pinfunction "~{RESET}_5") (pintype "open_collector"))
      (node (ref "U5") (pin "26") (pinfunction "RESET_26") (pintype "input"))
    )
    (net (code "125") (name "~{RFSH}") (class "Default")
      (node (ref "R10") (pin "2") (pinfunction "2_2") (pintype "passive"))
      (node (ref "U5") (pin "28") (pinfunction "RFSH_28") (pintype "output"))
      (node (ref "U6") (pin "6") (pinfunction "G1_6") (pintype "input"))
    )
    (net (code "126") (name "~{TZ_ROM_CS}") (class "Default")
      (node (ref "U10") (pin "4") (pinfunction "I0_4") (pintype "input"))
      (node (ref "U14") (pin "22") (pinfunction "~{CE}_22") (pintype "input"))
      (node (ref "U6") (pin "9") (pinfunction "Y6_9") (pintype "output"))
    )
    (net (code "127") (name "~{WAIT}") (class "Default")
      (node (ref "BUS") (pin "10") (pinfunction "S_10") (pintype "passive"))
      (node (ref "JP1") (pin "2") (pinfunction "2_2") (pintype "passive"))
      (node (ref "R11") (pin "2") (pinfunction "2_2") (pintype "passive"))
      (node (ref "U5") (pin "24") (pinfunction "WAIT_24") (pintype "input"))
    )
    (net (code "128") (name "~{WR}") (class "Default")
      (node (ref "R9") (pin "2") (pinfunction "2_2") (pintype "passive"))
      (node (ref "U10") (pin "1") (pinfunction "I0_1") (pintype "input"))
      (node (ref "U12") (pin "31") (pinfunction "~{WE}_31") (pintype "input"))
      (node (ref "U13") (pin "27") (pinfunction "~{WE}_27") (pintype "input"))
      (node (ref "U14") (pin "31") (pinfunction "~{WE}_31") (pintype "input"))
      (node (ref "U15") (pin "31") (pinfunction "~{WE}_31") (pintype "input"))
      (node (ref "U3") (pin "14") (pinfunction "B5_14") (pintype "bidirectional"))
      (node (ref "U5") (pin "22") (pinfunction "WR_22") (pintype "output"))
    )
  )
)
